# CuC_DataComm.net
KiCad netlist of a schematic drawn in Altium Designer
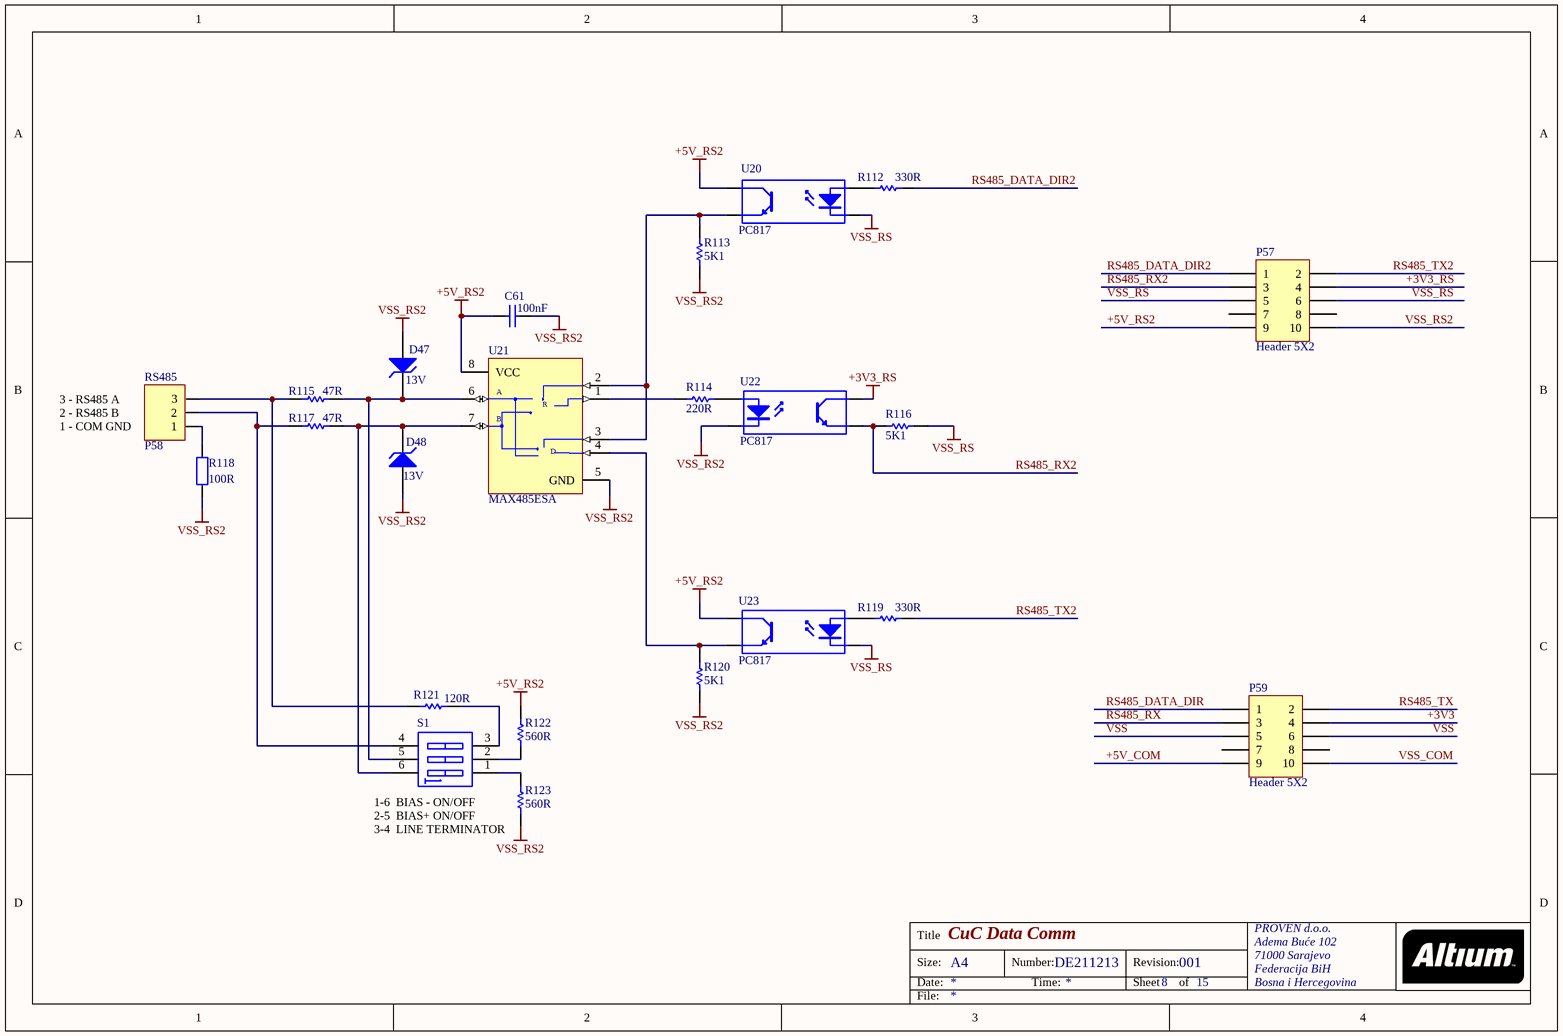
[diagram p0: CuC_DataComm.SchDoc]

(export (version "E")
  (design (tool "Eeschema 10.0.6"))
  (components
    (comp (ref "C61")
      (value "100nF")
      (footprint "1206")
      (description "Ceramic Chip Capacitor - Standard")
      (fields (field (name "PUBLISHER") "Altium Limited"))
      (libsource (lib "KEMET Chip Capacitor") (part "C1206"))
    )
    (comp (ref "D47")
      (value "13V")
      (footprint "Miscellaneous Devices:DO-35A")
      (description "Zener Diode")
      (fields (field (name "PUBLISHER") "Altium Limited"))
      (libsource (lib "Miscellaneous Devices") (part "D Zener"))
    )
    (comp (ref "D48")
      (value "13V")
      (footprint "Miscellaneous Devices:DO-35A")
      (description "Zener Diode")
      (fields (field (name "PUBLISHER") "Altium Limited"))
      (libsource (lib "Miscellaneous Devices") (part "D Zener"))
    )
    (comp (ref "P57")
      (value "Header 5X2")
      (footprint "HDR2X5")
      (description "Header, 5-Pin, Dual row")
      (fields (field (name "PUBLISHER") "Altium Limited"))
      (libsource (lib "Miscellaneous Connectors") (part "Header 5X2"))
    )
    (comp (ref "P58")
      (value "RS485")
      (footprint "TERMINAL BLOK 3")
      (description "3 pinski terminal blok konektor")
      (libsource (lib "ProjectLibrary") (part "TERMINAL BLOK 3"))
    )
    (comp (ref "P59")
      (value "Header 5X2")
      (footprint "HDR2X5")
      (description "Header, 5-Pin, Dual row")
      (fields (field (name "PUBLISHER") "Altium Limited"))
      (libsource (lib "Miscellaneous Connectors") (part "Header 5X2"))
    )
    (comp (ref "R112")
      (value "330R")
      (footprint "ERA-0805")
      (fields (field (name "PUBLISHER") "Altium Limited"))
      (libsource (lib "Panasonic Resistor") (part "ERA6Y"))
    )
    (comp (ref "R113")
      (value "5K1")
      (footprint "8-1206")
      (description "Thick Film Chip Resistor, 1 Ohm to 10M Ohm Range, 5% Tolerance, 1206 Size, 0.25 W")
      (fields (field (name "PUBLISHER") "Altium Limited"))
      (libsource (lib "Panasonic Resistor") (part "ERJ8GE"))
    )
    (comp (ref "R114")
      (value "220R")
      (footprint "ERA-0805")
      (fields (field (name "PUBLISHER") "Altium Limited"))
      (libsource (lib "Panasonic Resistor") (part "ERAS"))
    )
    (comp (ref "R115")
      (value "47R")
      (footprint "ERA-0805")
      (fields (field (name "PUBLISHER") "Altium Limited"))
      (libsource (lib "Panasonic Resistor") (part "ERAS"))
    )
    (comp (ref "R116")
      (value "5K1")
      (footprint "8-1206")
      (description "Thick Film Chip Resistor, 1 Ohm to 10M Ohm Range, 5% Tolerance, 1206 Size, 0.25 W")
      (fields (field (name "PUBLISHER") "Altium Limited"))
      (libsource (lib "Panasonic Resistor") (part "ERJ8GE"))
    )
    (comp (ref "R117")
      (value "47R")
      (footprint "ERA-0805")
      (fields (field (name "PUBLISHER") "Altium Limited"))
      (libsource (lib "Panasonic Resistor") (part "ERAS"))
    )
    (comp (ref "R118")
      (value "100R")
      (footprint "AXIAL-0.4")
      (description "Resistor")
      (fields (field (name "PUBLISHER") "Altium Limited"))
      (libsource (lib "Miscellaneous Devices") (part "Res2"))
    )
    (comp (ref "R119")
      (value "330R")
      (footprint "ERA-0805")
      (fields (field (name "PUBLISHER") "Altium Limited"))
      (libsource (lib "Panasonic Resistor") (part "ERA6Y"))
    )
    (comp (ref "R120")
      (value "5K1")
      (footprint "8-1206")
      (description "Thick Film Chip Resistor, 1 Ohm to 10M Ohm Range, 5% Tolerance, 1206 Size, 0.25 W")
      (fields (field (name "PUBLISHER") "Altium Limited"))
      (libsource (lib "Panasonic Resistor") (part "ERJ8GE"))
    )
    (comp (ref "R121")
      (value "120R")
      (footprint "ERA-0805")
      (fields (field (name "PUBLISHER") "Altium Limited"))
      (libsource (lib "Panasonic Resistor") (part "ERAS"))
    )
    (comp (ref "R122")
      (value "560R")
      (footprint "ERA-0805")
      (fields (field (name "PUBLISHER") "Altium Limited"))
      (libsource (lib "Panasonic Resistor") (part "ERAS"))
    )
    (comp (ref "R123")
      (value "560R")
      (footprint "ERA-0805")
      (fields (field (name "PUBLISHER") "Altium Limited"))
      (libsource (lib "Panasonic Resistor") (part "ERAS"))
    )
    (comp (ref "S1")
      (value "~")
      (footprint "DIP-6")
      (description "DIP Switch, 3 Position, SPST")
      (fields (field (name "PUBLISHER") "Altium Limited"))
      (libsource (lib "Miscellaneous Devices") (part "SW DIP-3"))
    )
    (comp (ref "U20")
      (value "PC817")
      (footprint "DIP-4")
      (description "4-Pin Phototransistor Optocoupler")
      (fields (field (name "PUBLISHER") "Altium Limited"))
      (libsource (lib "Miscellaneous Devices") (part "Optoisolator1"))
    )
    (comp (ref "U21")
      (value "MAX485ESA")
      (footprint "NSO8_N")
      (description "Low-Power, Slew-Rate-Limited RS-485/RS-422 Transceiver")
      (fields (field (name "PUBLISHER") "Altium Limited"))
      (libsource (lib "Maxim Communication Transceiver") (part "MAX485ESA"))
    )
    (comp (ref "U22")
      (value "PC817")
      (footprint "DIP-4")
      (description "4-Pin Phototransistor Optocoupler")
      (fields (field (name "PUBLISHER") "Altium Limited"))
      (libsource (lib "Miscellaneous Devices") (part "Optoisolator1"))
    )
    (comp (ref "U23")
      (value "PC817")
      (footprint "DIP-4")
      (description "4-Pin Phototransistor Optocoupler")
      (fields (field (name "PUBLISHER") "Altium Limited"))
      (libsource (lib "Miscellaneous Devices") (part "Optoisolator1"))
    )
  )
  (nets
    (net (code "1") (name "+3V3_RS") (class "Default")
      (node (ref "P57") (pin "4") (pinfunction "4_4") (pintype "passive"))
      (node (ref "U22") (pin "4") (pinfunction "C_4") (pintype "passive"))
    )
    (net (code "2") (name "+5V_RS2") (class "Default")
      (node (ref "C61") (pin "2") (pinfunction "2_2") (pintype "passive"))
      (node (ref "P57") (pin "9") (pinfunction "9_9") (pintype "passive"))
      (node (ref "R122") (pin "2") (pinfunction "2_2") (pintype "passive"))
      (node (ref "U20") (pin "4") (pinfunction "C_4") (pintype "passive"))
      (node (ref "U21") (pin "8") (pinfunction "VCC_8") (pintype "power_in"))
      (node (ref "U23") (pin "4") (pinfunction "C_4") (pintype "passive"))
    )
    (net (code "3") (name "/+3V3") (class "Default")
      (node (ref "P59") (pin "4") (pinfunction "4_4") (pintype "passive"))
    )
    (net (code "4") (name "/+5V_COM") (class "Default")
      (node (ref "P59") (pin "9") (pinfunction "9_9") (pintype "passive"))
    )
    (net (code "5") (name "/RS485_DATA_DIR") (class "Default")
      (node (ref "P59") (pin "1") (pinfunction "1_1") (pintype "passive"))
    )
    (net (code "6") (name "/RS485_DATA_DIR2") (class "Default")
      (node (ref "P57") (pin "1") (pinfunction "1_1") (pintype "passive"))
      (node (ref "R112") (pin "2") (pinfunction "2_2") (pintype "passive"))
    )
    (net (code "7") (name "/RS485_RX") (class "Default")
      (node (ref "P59") (pin "3") (pinfunction "3_3") (pintype "passive"))
    )
    (net (code "8") (name "/RS485_RX2") (class "Default")
      (node (ref "P57") (pin "3") (pinfunction "3_3") (pintype "passive"))
      (node (ref "R116") (pin "1") (pinfunction "1_1") (pintype "passive"))
      (node (ref "U22") (pin "3") (pinfunction "E_3") (pintype "passive"))
    )
    (net (code "9") (name "/RS485_TX") (class "Default")
      (node (ref "P59") (pin "2") (pinfunction "2_2") (pintype "passive"))
    )
    (net (code "10") (name "/RS485_TX2") (class "Default")
      (node (ref "P57") (pin "2") (pinfunction "2_2") (pintype "passive"))
      (node (ref "R119") (pin "2") (pinfunction "2_2") (pintype "passive"))
    )
    (net (code "11") (name "/VSS") (class "Default")
      (node (ref "P59") (pin "5") (pinfunction "5_5") (pintype "passive"))
      (node (ref "P59") (pin "6") (pinfunction "6_6") (pintype "passive"))
    )
    (net (code "12") (name "/VSS_COM") (class "Default")
      (node (ref "P59") (pin "10") (pinfunction "10_10") (pintype "passive"))
    )
    (net (code "13") (name "Net-(D47-K)") (class "Default")
      (node (ref "D47") (pin "2") (pinfunction "K_2") (pintype "passive"))
      (node (ref "R115") (pin "2") (pinfunction "2_2") (pintype "passive"))
      (node (ref "S1") (pin "5") (pinfunction "B2_5") (pintype "passive"))
      (node (ref "U21") (pin "6") (pinfunction "A_6") (pintype "bidirectional"))
    )
    (net (code "14") (name "Net-(D48-K)") (class "Default")
      (node (ref "D48") (pin "2") (pinfunction "K_2") (pintype "passive"))
      (node (ref "R117") (pin "2") (pinfunction "2_2") (pintype "passive"))
      (node (ref "S1") (pin "6") (pinfunction "B1_6") (pintype "passive"))
      (node (ref "U21") (pin "7") (pinfunction "B_7") (pintype "bidirectional"))
    )
    (net (code "15") (name "Net-(P58-Pad1)") (class "Default")
      (node (ref "P58") (pin "1") (pinfunction "1_1") (pintype "passive"))
      (node (ref "R118") (pin "2") (pinfunction "2_2") (pintype "passive"))
    )
    (net (code "16") (name "Net-(P58-Pad3)") (class "Default")
      (node (ref "P58") (pin "3") (pinfunction "3_3") (pintype "passive"))
      (node (ref "R115") (pin "1") (pinfunction "1_1") (pintype "passive"))
      (node (ref "R121") (pin "1") (pinfunction "1_1") (pintype "passive"))
    )
    (net (code "17") (name "Net-(S1-A1)") (class "Default")
      (node (ref "R123") (pin "2") (pinfunction "2_2") (pintype "passive"))
      (node (ref "S1") (pin "1") (pinfunction "A1_1") (pintype "passive"))
    )
    (net (code "18") (name "Net-(S1-A2)") (class "Default")
      (node (ref "R122") (pin "1") (pinfunction "1_1") (pintype "passive"))
      (node (ref "S1") (pin "2") (pinfunction "A2_2") (pintype "passive"))
    )
    (net (code "19") (name "Net-(S1-A3)") (class "Default")
      (node (ref "R121") (pin "2") (pinfunction "2_2") (pintype "passive"))
      (node (ref "S1") (pin "3") (pinfunction "A3_3") (pintype "passive"))
    )
    (net (code "20") (name "Net-(S1-B3)") (class "Default")
      (node (ref "P58") (pin "2") (pinfunction "2_2") (pintype "passive"))
      (node (ref "R117") (pin "1") (pinfunction "1_1") (pintype "passive"))
      (node (ref "S1") (pin "4") (pinfunction "B3_4") (pintype "passive"))
    )
    (net (code "21") (name "Net-(U20-A)") (class "Default")
      (node (ref "R112") (pin "1") (pinfunction "1_1") (pintype "passive"))
      (node (ref "U20") (pin "1") (pinfunction "A_1") (pintype "passive"))
    )
    (net (code "22") (name "Net-(U20-E)") (class "Default")
      (node (ref "R113") (pin "2") (pinfunction "2_2") (pintype "passive"))
      (node (ref "U20") (pin "3") (pinfunction "E_3") (pintype "passive"))
      (node (ref "U21") (pin "2") (pinfunction "~{RE}_2") (pintype "input"))
      (node (ref "U21") (pin "3") (pinfunction "DE_3") (pintype "input"))
    )
    (net (code "23") (name "Net-(U21-DI)") (class "Default")
      (node (ref "R120") (pin "2") (pinfunction "2_2") (pintype "passive"))
      (node (ref "U21") (pin "4") (pinfunction "DI_4") (pintype "input"))
      (node (ref "U23") (pin "3") (pinfunction "E_3") (pintype "passive"))
    )
    (net (code "24") (name "Net-(U21-RO)") (class "Default")
      (node (ref "R114") (pin "2") (pinfunction "2_2") (pintype "passive"))
      (node (ref "U21") (pin "1") (pinfunction "RO_1") (pintype "output"))
    )
    (net (code "25") (name "Net-(U22-A)") (class "Default")
      (node (ref "R114") (pin "1") (pinfunction "1_1") (pintype "passive"))
      (node (ref "U22") (pin "1") (pinfunction "A_1") (pintype "passive"))
    )
    (net (code "26") (name "Net-(U23-A)") (class "Default")
      (node (ref "R119") (pin "1") (pinfunction "1_1") (pintype "passive"))
      (node (ref "U23") (pin "1") (pinfunction "A_1") (pintype "passive"))
    )
    (net (code "27") (name "VSS_RS") (class "Default")
      (node (ref "P57") (pin "5") (pinfunction "5_5") (pintype "passive"))
      (node (ref "P57") (pin "6") (pinfunction "6_6") (pintype "passive"))
      (node (ref "R116") (pin "2") (pinfunction "2_2") (pintype "passive"))
      (node (ref "U20") (pin "2") (pinfunction "K_2") (pintype "passive"))
      (node (ref "U23") (pin "2") (pinfunction "K_2") (pintype "passive"))
    )
    (net (code "28") (name "VSS_RS2") (class "Default")
      (node (ref "C61") (pin "1") (pinfunction "1_1") (pintype "passive"))
      (node (ref "D47") (pin "1") (pinfunction "A_1") (pintype "passive"))
      (node (ref "D48") (pin "1") (pinfunction "A_1") (pintype "passive"))
      (node (ref "P57") (pin "10") (pinfunction "10_10") (pintype "passive"))
      (node (ref "R113") (pin "1") (pinfunction "1_1") (pintype "passive"))
      (node (ref "R118") (pin "1") (pinfunction "1_1") (pintype "passive"))
      (node (ref "R120") (pin "1") (pinfunction "1_1") (pintype "passive"))
      (node (ref "R123") (pin "1") (pinfunction "1_1") (pintype "passive"))
      (node (ref "U21") (pin "5") (pinfunction "GND_5") (pintype "power_in"))
      (node (ref "U22") (pin "2") (pinfunction "K_2") (pintype "passive"))
    )
    (net (code "29") (name "unconnected-(P57-Pad7)") (class "Default")
      (node (ref "P57") (pin "7") (pinfunction "7_7") (pintype "passive"))
    )
    (net (code "30") (name "unconnected-(P57-Pad8)") (class "Default")
      (node (ref "P57") (pin "8") (pinfunction "8_8") (pintype "passive"))
    )
    (net (code "31") (name "unconnected-(P59-Pad7)") (class "Default")
      (node (ref "P59") (pin "7") (pinfunction "7_7") (pintype "passive"))
    )
    (net (code "32") (name "unconnected-(P59-Pad8)") (class "Default")
      (node (ref "P59") (pin "8") (pinfunction "8_8") (pintype "passive"))
    )
  )
)
